# garage_door_opener_v1_3_2015_07_16.net
KiCad netlist of a schematic drawn in EAGLE
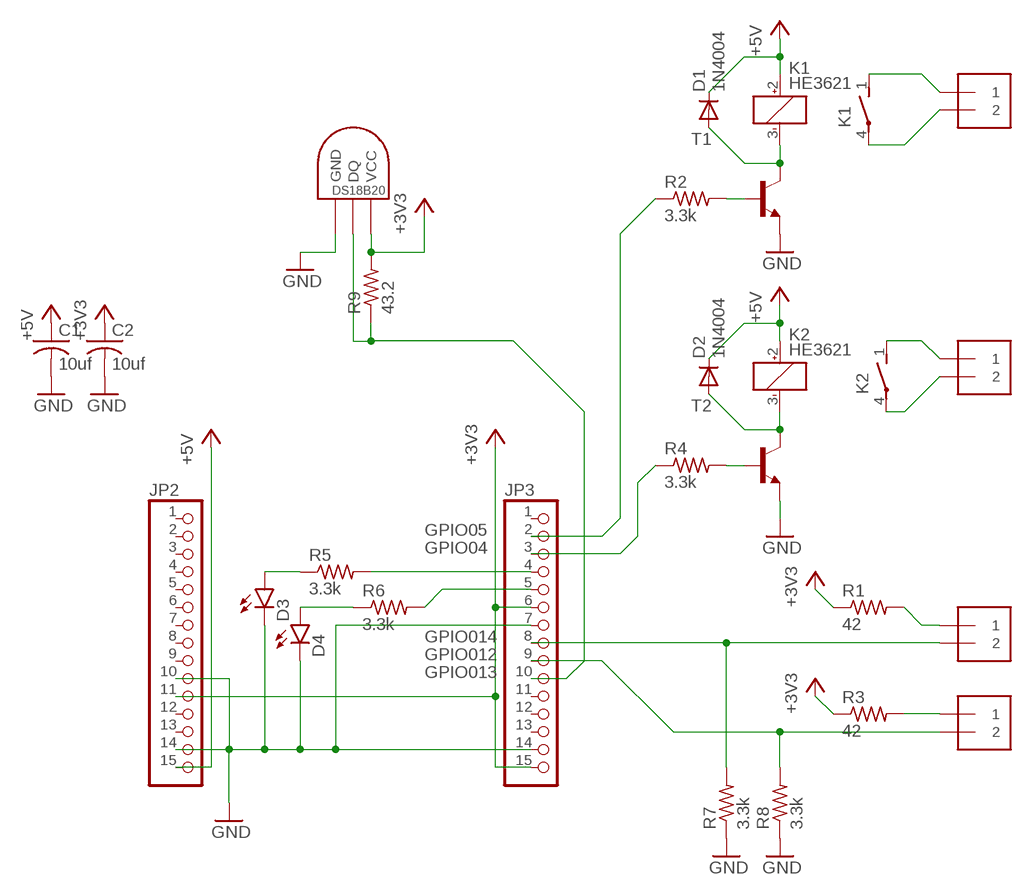
[diagram p0: schematic, sheet 1]

(export (version "E")
  (design (tool "Eeschema 10.0.6"))
  (components
    (comp (ref "C1")
      (value "10uf")
      (footprint "eagle-import:C0603")
      (libsource (lib "eagle-import") (part "C-USC0603"))
    )
    (comp (ref "C2")
      (value "10uf")
      (footprint "eagle-import:C0603")
      (libsource (lib "eagle-import") (part "C-USC0603"))
    )
    (comp (ref "D1")
      (value "1N4004")
      (footprint "eagle-import:DO214BA")
      (libsource (lib "eagle-import") (part "DIODE-DO214BA"))
    )
    (comp (ref "D2")
      (value "1N4004")
      (footprint "eagle-import:DO214BA")
      (libsource (lib "eagle-import") (part "DIODE-DO214BA"))
    )
    (comp (ref "D3")
      (value "LED0603")
      (footprint "eagle-import:LED-0603")
      (libsource (lib "eagle-import") (part "LED0603"))
    )
    (comp (ref "D4")
      (value "LED0603")
      (footprint "eagle-import:LED-0603")
      (libsource (lib "eagle-import") (part "LED0603"))
    )
    (comp (ref "DS18B20")
      (value "DS18B20TO92")
      (footprint "eagle-import:DS1820")
      (libsource (lib "eagle-import") (part "DS1820TO92"))
    )
    (comp (ref "JP2")
      (value "PINHD-1X15")
      (footprint "eagle-import:1X15")
      (libsource (lib "eagle-import") (part "PINHD-1X15"))
    )
    (comp (ref "JP3")
      (value "PINHD-1X15")
      (footprint "eagle-import:1X15")
      (libsource (lib "eagle-import") (part "PINHD-1X15"))
    )
    (comp (ref "K1")
      (value "HE3621")
      (footprint "eagle-import:HE3621")
      (fields
        (field (name "MF") "HAMLIN")
        (field (name "MPN") "HE3621A2410")
        (field (name "MPN_1") "HE3621A0510")
      )
      (libsource (lib "eagle-import") (part "HE3621"))
    )
    (comp (ref "K2")
      (value "HE3621")
      (footprint "eagle-import:HE3621")
      (fields
        (field (name "MF") "HAMLIN")
        (field (name "MPN") "HE3621A2410")
        (field (name "MPN_1") "HE3621A0510")
      )
      (libsource (lib "eagle-import") (part "HE3621"))
    )
    (comp (ref "OPEN1")
      (value "1X2-3.5MM")
      (footprint "eagle-import:1X2-3.5MM")
      (fields (field (name "MPN") "OSTTE020161"))
      (libsource (lib "eagle-import") (part "1X2-3.5MM"))
    )
    (comp (ref "OPEN2")
      (value "1X2-3.5MM")
      (footprint "eagle-import:1X2-3.5MM")
      (fields (field (name "MPN") "OSTTE020161"))
      (libsource (lib "eagle-import") (part "1X2-3.5MM"))
    )
    (comp (ref "R1")
      (value "42")
      (footprint "eagle-import:R0603")
      (libsource (lib "eagle-import") (part "R-US_R0603"))
    )
    (comp (ref "R2")
      (value "3.3k")
      (footprint "eagle-import:R0603")
      (libsource (lib "eagle-import") (part "R-US_R0603"))
    )
    (comp (ref "R3")
      (value "42")
      (footprint "eagle-import:R0603")
      (libsource (lib "eagle-import") (part "R-US_R0603"))
    )
    (comp (ref "R4")
      (value "3.3k")
      (footprint "eagle-import:R0603")
      (libsource (lib "eagle-import") (part "R-US_R0603"))
    )
    (comp (ref "R5")
      (value "3.3k")
      (footprint "eagle-import:R0603")
      (libsource (lib "eagle-import") (part "R-US_R0603"))
    )
    (comp (ref "R6")
      (value "3.3k")
      (footprint "eagle-import:R0603")
      (libsource (lib "eagle-import") (part "R-US_R0603"))
    )
    (comp (ref "R7")
      (value "3.3k")
      (footprint "eagle-import:R0603")
      (libsource (lib "eagle-import") (part "R-US_R0603"))
    )
    (comp (ref "R8")
      (value "3.3k")
      (footprint "eagle-import:R0603")
      (libsource (lib "eagle-import") (part "R-US_R0603"))
    )
    (comp (ref "R9")
      (value "43.2")
      (footprint "eagle-import:R0603")
      (libsource (lib "eagle-import") (part "R-US_R0603"))
    )
    (comp (ref "SENS1")
      (value "1X2-3.5MM")
      (footprint "eagle-import:1X2-3.5MM")
      (fields (field (name "MPN") "OSTTE020161"))
      (libsource (lib "eagle-import") (part "1X2-3.5MM"))
    )
    (comp (ref "SENS2")
      (value "1X2-3.5MM")
      (footprint "eagle-import:1X2-3.5MM")
      (fields (field (name "MPN") "OSTTE020161"))
      (libsource (lib "eagle-import") (part "1X2-3.5MM"))
    )
    (comp (ref "T1")
      (value "MMBT3904LT1-NPN-SOT23-BEC")
      (footprint "eagle-import:SOT23-BEC")
      (fields (field (name "MPN") "MMBT2222A"))
      (libsource (lib "eagle-import") (part "-NPN-SOT23-BECMMBT3904LT1"))
    )
    (comp (ref "T2")
      (value "MMBT3904LT1-NPN-SOT23-BEC")
      (footprint "eagle-import:SOT23-BEC")
      (fields (field (name "MPN") "MMBT2222A"))
      (libsource (lib "eagle-import") (part "-NPN-SOT23-BECMMBT3904LT1"))
    )
  )
  (nets
    (net (code "1") (name "+3V3") (class "Default")
      (node (ref "C2") (pin "1") (pinfunction "1_1") (pintype "passive"))
      (node (ref "DS18B20") (pin "VDD") (pinfunction "VCC_VDD") (pintype "power_in"))
      (node (ref "JP2") (pin "11") (pinfunction "11_11") (pintype "passive"))
      (node (ref "JP3") (pin "15") (pinfunction "15_15") (pintype "passive"))
      (node (ref "JP3") (pin "6") (pinfunction "6_6") (pintype "passive"))
      (node (ref "R1") (pin "1") (pinfunction "1_1") (pintype "passive"))
      (node (ref "R3") (pin "1") (pinfunction "1_1") (pintype "passive"))
      (node (ref "R9") (pin "2") (pinfunction "2_2") (pintype "passive"))
    )
    (net (code "2") (name "+5V") (class "Default")
      (node (ref "C1") (pin "1") (pinfunction "1_1") (pintype "passive"))
      (node (ref "D1") (pin "C") (pinfunction "C_C") (pintype "passive"))
      (node (ref "D2") (pin "C") (pinfunction "C_C") (pintype "passive"))
      (node (ref "JP2") (pin "15") (pinfunction "15_15") (pintype "passive"))
      (node (ref "K1") (pin "2") (pinfunction "+_2") (pintype "passive"))
      (node (ref "K2") (pin "2") (pinfunction "+_2") (pintype "passive"))
    )
    (net (code "3") (name "GND") (class "Default")
      (node (ref "C1") (pin "2") (pinfunction "2_2") (pintype "passive"))
      (node (ref "C2") (pin "2") (pinfunction "2_2") (pintype "passive"))
      (node (ref "D3") (pin "C") (pinfunction "C_C") (pintype "passive"))
      (node (ref "D4") (pin "C") (pinfunction "C_C") (pintype "passive"))
      (node (ref "DS18B20") (pin "GND") (pinfunction "GND_GND") (pintype "power_in"))
      (node (ref "JP2") (pin "10") (pinfunction "10_10") (pintype "passive"))
      (node (ref "JP2") (pin "14") (pinfunction "14_14") (pintype "passive"))
      (node (ref "JP3") (pin "14") (pinfunction "14_14") (pintype "passive"))
      (node (ref "JP3") (pin "7") (pinfunction "7_7") (pintype "passive"))
      (node (ref "R7") (pin "1") (pinfunction "1_1") (pintype "passive"))
      (node (ref "R8") (pin "1") (pinfunction "1_1") (pintype "passive"))
      (node (ref "T1") (pin "E") (pinfunction "E_E") (pintype "passive"))
      (node (ref "T2") (pin "E") (pinfunction "E_E") (pintype "passive"))
    )
    (net (code "4") (name "Net-(D3-PadA)") (class "Default")
      (node (ref "D3") (pin "A") (pinfunction "A_A") (pintype "passive"))
      (node (ref "R5") (pin "1") (pinfunction "1_1") (pintype "passive"))
    )
    (net (code "5") (name "Net-(D4-PadA)") (class "Default")
      (node (ref "D4") (pin "A") (pinfunction "A_A") (pintype "passive"))
      (node (ref "R6") (pin "1") (pinfunction "1_1") (pintype "passive"))
    )
    (net (code "6") (name "Net-(DS18B20-PadDQ)") (class "Default")
      (node (ref "DS18B20") (pin "DQ") (pinfunction "DQ_DQ") (pintype "bidirectional"))
      (node (ref "JP3") (pin "10") (pinfunction "10_10") (pintype "passive"))
      (node (ref "R9") (pin "1") (pinfunction "1_1") (pintype "passive"))
    )
    (net (code "7") (name "Net-(JP3-Pad2)") (class "Default")
      (node (ref "JP3") (pin "2") (pinfunction "2_2") (pintype "passive"))
      (node (ref "R2") (pin "1") (pinfunction "1_1") (pintype "passive"))
    )
    (net (code "8") (name "Net-(JP3-Pad3)") (class "Default")
      (node (ref "JP3") (pin "3") (pinfunction "3_3") (pintype "passive"))
      (node (ref "R4") (pin "1") (pinfunction "1_1") (pintype "passive"))
    )
    (net (code "9") (name "Net-(JP3-Pad4)") (class "Default")
      (node (ref "JP3") (pin "4") (pinfunction "4_4") (pintype "passive"))
      (node (ref "R5") (pin "2") (pinfunction "2_2") (pintype "passive"))
    )
    (net (code "10") (name "Net-(JP3-Pad5)") (class "Default")
      (node (ref "JP3") (pin "5") (pinfunction "5_5") (pintype "passive"))
      (node (ref "R6") (pin "2") (pinfunction "2_2") (pintype "passive"))
    )
    (net (code "11") (name "Net-(JP3-Pad8)") (class "Default")
      (node (ref "JP3") (pin "8") (pinfunction "8_8") (pintype "passive"))
      (node (ref "R7") (pin "2") (pinfunction "2_2") (pintype "passive"))
      (node (ref "SENS1") (pin "2") (pinfunction "2_2") (pintype "passive"))
    )
    (net (code "12") (name "Net-(JP3-Pad9)") (class "Default")
      (node (ref "JP3") (pin "9") (pinfunction "9_9") (pintype "passive"))
      (node (ref "R8") (pin "2") (pinfunction "2_2") (pintype "passive"))
      (node (ref "SENS2") (pin "2") (pinfunction "2_2") (pintype "passive"))
    )
    (net (code "13") (name "Net-(K1A--)") (class "Default")
      (node (ref "D1") (pin "A") (pinfunction "A_A") (pintype "passive"))
      (node (ref "K1") (pin "3") (pinfunction "-_3") (pintype "passive"))
      (node (ref "T1") (pin "C") (pinfunction "C_C") (pintype "passive"))
    )
    (net (code "14") (name "Net-(K1B-P)") (class "Default")
      (node (ref "K1") (pin "4") (pinfunction "P_4") (pintype "passive"))
      (node (ref "OPEN1") (pin "2") (pinfunction "2_2") (pintype "passive"))
    )
    (net (code "15") (name "Net-(K1B-S)") (class "Default")
      (node (ref "K1") (pin "1") (pinfunction "S_1") (pintype "passive"))
      (node (ref "OPEN1") (pin "1") (pinfunction "1_1") (pintype "passive"))
    )
    (net (code "16") (name "Net-(K2A--)") (class "Default")
      (node (ref "D2") (pin "A") (pinfunction "A_A") (pintype "passive"))
      (node (ref "K2") (pin "3") (pinfunction "-_3") (pintype "passive"))
      (node (ref "T2") (pin "C") (pinfunction "C_C") (pintype "passive"))
    )
    (net (code "17") (name "Net-(K2B-P)") (class "Default")
      (node (ref "K2") (pin "4") (pinfunction "P_4") (pintype "passive"))
      (node (ref "OPEN2") (pin "2") (pinfunction "2_2") (pintype "passive"))
    )
    (net (code "18") (name "Net-(K2B-S)") (class "Default")
      (node (ref "K2") (pin "1") (pinfunction "S_1") (pintype "passive"))
      (node (ref "OPEN2") (pin "1") (pinfunction "1_1") (pintype "passive"))
    )
    (net (code "19") (name "Net-(R1-Pad2)") (class "Default")
      (node (ref "R1") (pin "2") (pinfunction "2_2") (pintype "passive"))
      (node (ref "SENS1") (pin "1") (pinfunction "1_1") (pintype "passive"))
    )
    (net (code "20") (name "Net-(R2-Pad2)") (class "Default")
      (node (ref "R2") (pin "2") (pinfunction "2_2") (pintype "passive"))
      (node (ref "T1") (pin "B") (pinfunction "B_B") (pintype "passive"))
    )
    (net (code "21") (name "Net-(R3-Pad2)") (class "Default")
      (node (ref "R3") (pin "2") (pinfunction "2_2") (pintype "passive"))
      (node (ref "SENS2") (pin "1") (pinfunction "1_1") (pintype "passive"))
    )
    (net (code "22") (name "Net-(R4-Pad2)") (class "Default")
      (node (ref "R4") (pin "2") (pinfunction "2_2") (pintype "passive"))
      (node (ref "T2") (pin "B") (pinfunction "B_B") (pintype "passive"))
    )
    (net (code "23") (name "unconnected-(JP2-Pad1)") (class "Default")
      (node (ref "JP2") (pin "1") (pinfunction "1_1") (pintype "passive"))
    )
    (net (code "24") (name "unconnected-(JP2-Pad2)") (class "Default")
      (node (ref "JP2") (pin "2") (pinfunction "2_2") (pintype "passive"))
    )
    (net (code "25") (name "unconnected-(JP2-Pad3)") (class "Default")
      (node (ref "JP2") (pin "3") (pinfunction "3_3") (pintype "passive"))
    )
    (net (code "26") (name "unconnected-(JP2-Pad4)") (class "Default")
      (node (ref "JP2") (pin "4") (pinfunction "4_4") (pintype "passive"))
    )
    (net (code "27") (name "unconnected-(JP2-Pad5)") (class "Default")
      (node (ref "JP2") (pin "5") (pinfunction "5_5") (pintype "passive"))
    )
    (net (code "28") (name "unconnected-(JP2-Pad6)") (class "Default")
      (node (ref "JP2") (pin "6") (pinfunction "6_6") (pintype "passive"))
    )
    (net (code "29") (name "unconnected-(JP2-Pad7)") (class "Default")
      (node (ref "JP2") (pin "7") (pinfunction "7_7") (pintype "passive"))
    )
    (net (code "30") (name "unconnected-(JP2-Pad8)") (class "Default")
      (node (ref "JP2") (pin "8") (pinfunction "8_8") (pintype "passive"))
    )
    (net (code "31") (name "unconnected-(JP2-Pad9)") (class "Default")
      (node (ref "JP2") (pin "9") (pinfunction "9_9") (pintype "passive"))
    )
    (net (code "32") (name "unconnected-(JP2-Pad12)") (class "Default")
      (node (ref "JP2") (pin "12") (pinfunction "12_12") (pintype "passive"))
    )
    (net (code "33") (name "unconnected-(JP2-Pad13)") (class "Default")
      (node (ref "JP2") (pin "13") (pinfunction "13_13") (pintype "passive"))
    )
    (net (code "34") (name "unconnected-(JP3-Pad1)") (class "Default")
      (node (ref "JP3") (pin "1") (pinfunction "1_1") (pintype "passive"))
    )
    (net (code "35") (name "unconnected-(JP3-Pad11)") (class "Default")
      (node (ref "JP3") (pin "11") (pinfunction "11_11") (pintype "passive"))
    )
    (net (code "36") (name "unconnected-(JP3-Pad12)") (class "Default")
      (node (ref "JP3") (pin "12") (pinfunction "12_12") (pintype "passive"))
    )
    (net (code "37") (name "unconnected-(JP3-Pad13)") (class "Default")
      (node (ref "JP3") (pin "13") (pinfunction "13_13") (pintype "passive"))
    )
  )
)
